# purple_v2.net
KiCad netlist of a schematic drawn in EAGLE
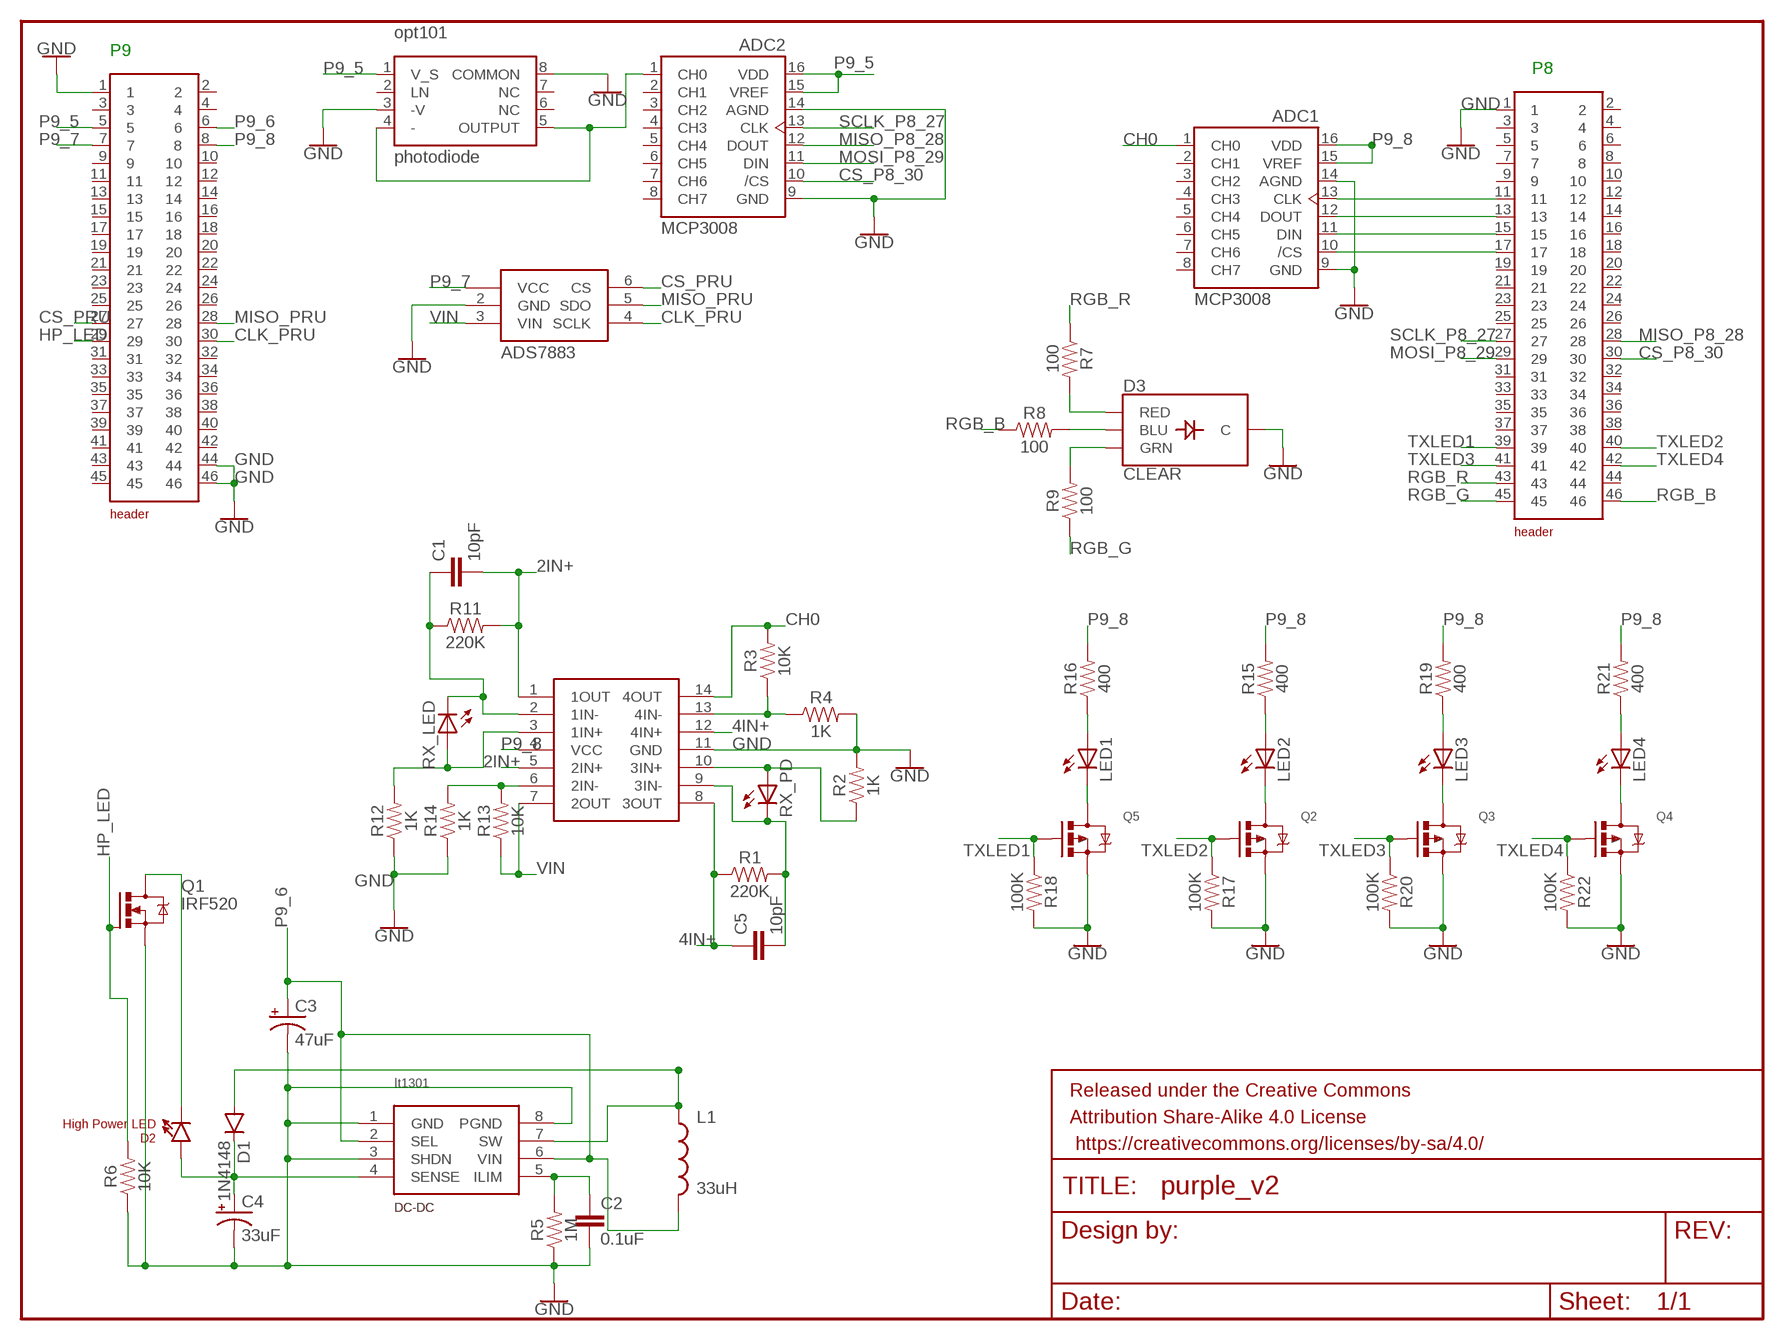
[diagram p0: schematic, sheet 1]

(export (version "E")
  (design (tool "Eeschema 10.0.6"))
  (components
    (comp (ref "ADC1")
      (value "MCP3008-SO16")
      (footprint "eagle-import:SO16")
      (libsource (lib "eagle-import") (part "MCP3008-SO16"))
    )
    (comp (ref "ADC2")
      (value "MCP3008-SO16")
      (footprint "eagle-import:SO16")
      (libsource (lib "eagle-import") (part "MCP3008-SO16"))
    )
    (comp (ref "C1")
      (value "10pF")
      (footprint "eagle-import:0603")
      (libsource (lib "eagle-import") (part "10PF-0603-50V-5%"))
    )
    (comp (ref "C2")
      (value "0.1uF")
      (footprint "eagle-import:CAP-PTH-SMALL")
      (libsource (lib "eagle-import") (part "CAPPTH"))
    )
    (comp (ref "C3")
      (value "47uF")
      (footprint "eagle-import:CPOL-RADIAL-10UF-25V")
      (libsource (lib "eagle-import") (part "CAP_POLPTH2"))
    )
    (comp (ref "C4")
      (value "33uF")
      (footprint "eagle-import:CPOL-RADIAL-10UF-25V")
      (libsource (lib "eagle-import") (part "CAP_POLPTH2"))
    )
    (comp (ref "C5")
      (value "10pF")
      (footprint "eagle-import:0603")
      (libsource (lib "eagle-import") (part "10PF-0603-50V-5%"))
    )
    (comp (ref "D1")
      (value "1N4148")
      (footprint "eagle-import:DIODE-1N4148")
      (libsource (lib "eagle-import") (part "DIODE1N4148"))
    )
    (comp (ref "D2")
      (value "High Power LED")
      (footprint "eagle-import:LTE-302")
      (libsource (lib "eagle-import") (part "LTE-302"))
    )
    (comp (ref "D3")
      (value "CLEAR")
      (footprint "eagle-import:LED-RGB-THRU")
      (libsource (lib "eagle-import") (part "LED-RGB-CCCLEAR"))
    )
    (comp (ref "FRAME1")
      (value "FRAME-LETTERNO_PACKAGE")
      (footprint "eagle-import:DUMMY")
      (fields (field (name "DESIGNER") "Nobody"))
      (libsource (lib "eagle-import") (part "FRAME-LETTERNO_PACKAGE"))
    )
    (comp (ref "J1")
      (value "223")
      (footprint "eagle-import:2_23")
      (libsource (lib "eagle-import") (part "223"))
    )
    (comp (ref "J2")
      (value "223")
      (footprint "eagle-import:2_23")
      (libsource (lib "eagle-import") (part "223"))
    )
    (comp (ref "L1")
      (value "33uH")
      (footprint "eagle-import:RLB0912")
      (libsource (lib "eagle-import") (part "INDUCTORRLB0912"))
    )
    (comp (ref "LED1")
      (value "LED5MM")
      (footprint "eagle-import:LED5MM")
      (libsource (lib "eagle-import") (part "LED5MM"))
    )
    (comp (ref "LED2")
      (value "LED5MM")
      (footprint "eagle-import:LED5MM")
      (libsource (lib "eagle-import") (part "LED5MM"))
    )
    (comp (ref "LED3")
      (value "LED5MM")
      (footprint "eagle-import:LED5MM")
      (libsource (lib "eagle-import") (part "LED5MM"))
    )
    (comp (ref "LED4")
      (value "LED5MM")
      (footprint "eagle-import:LED5MM")
      (libsource (lib "eagle-import") (part "LED5MM"))
    )
    (comp (ref "OP-AMP")
      (value "TLC2274-SO14")
      (footprint "eagle-import:SO14")
      (libsource (lib "eagle-import") (part "TLC2274-SO14"))
    )
    (comp (ref "Q1")
      (value "IRF520")
      (footprint "eagle-import:TO220BV")
      (libsource (lib "eagle-import") (part "IRF520"))
    )
    (comp (ref "Q2")
      (value "MOSFET-PCHANNEL")
      (footprint "eagle-import:SOT23-3")
      (libsource (lib "eagle-import") (part "MOSFET-PCHANNEL"))
    )
    (comp (ref "Q3")
      (value "MOSFET-PCHANNEL")
      (footprint "eagle-import:SOT23-3")
      (libsource (lib "eagle-import") (part "MOSFET-PCHANNEL"))
    )
    (comp (ref "Q4")
      (value "MOSFET-PCHANNEL")
      (footprint "eagle-import:SOT23-3")
      (libsource (lib "eagle-import") (part "MOSFET-PCHANNEL"))
    )
    (comp (ref "Q5")
      (value "MOSFET-PCHANNEL")
      (footprint "eagle-import:SOT23-3")
      (libsource (lib "eagle-import") (part "MOSFET-PCHANNEL"))
    )
    (comp (ref "R1")
      (value "220K")
      (footprint "eagle-import:0805")
      (libsource (lib "eagle-import") (part "0.3OHM-0805-1/8W-1%"))
    )
    (comp (ref "R2")
      (value "1K")
      (footprint "eagle-import:0805")
      (libsource (lib "eagle-import") (part "0.3OHM-0805-1/8W-1%"))
    )
    (comp (ref "R3")
      (value "10K")
      (footprint "eagle-import:0805")
      (libsource (lib "eagle-import") (part "0.3OHM-0805-1/8W-1%"))
    )
    (comp (ref "R4")
      (value "1K")
      (footprint "eagle-import:0805")
      (libsource (lib "eagle-import") (part "0.3OHM-0805-1/8W-1%"))
    )
    (comp (ref "R5")
      (value "1M")
      (footprint "eagle-import:0805")
      (libsource (lib "eagle-import") (part "0.3OHM-0805-1/8W-1%"))
    )
    (comp (ref "R6")
      (value "10K")
      (footprint "eagle-import:0805")
      (libsource (lib "eagle-import") (part "0.3OHM-0805-1/8W-1%"))
    )
    (comp (ref "R7")
      (value "100")
      (footprint "eagle-import:0805")
      (libsource (lib "eagle-import") (part "0.3OHM-0805-1/8W-1%"))
    )
    (comp (ref "R8")
      (value "100")
      (footprint "eagle-import:0805")
      (libsource (lib "eagle-import") (part "0.3OHM-0805-1/8W-1%"))
    )
    (comp (ref "R9")
      (value "100")
      (footprint "eagle-import:0805")
      (libsource (lib "eagle-import") (part "0.3OHM-0805-1/8W-1%"))
    )
    (comp (ref "R11")
      (value "220K")
      (footprint "eagle-import:0805")
      (libsource (lib "eagle-import") (part "0.3OHM-0805-1/8W-1%"))
    )
    (comp (ref "R12")
      (value "1K")
      (footprint "eagle-import:0805")
      (libsource (lib "eagle-import") (part "0.3OHM-0805-1/8W-1%"))
    )
    (comp (ref "R13")
      (value "10K")
      (footprint "eagle-import:0805")
      (libsource (lib "eagle-import") (part "0.3OHM-0805-1/8W-1%"))
    )
    (comp (ref "R14")
      (value "1K")
      (footprint "eagle-import:0805")
      (libsource (lib "eagle-import") (part "0.3OHM-0805-1/8W-1%"))
    )
    (comp (ref "R15")
      (value "400")
      (footprint "eagle-import:0805")
      (libsource (lib "eagle-import") (part "0.3OHM-0805-1/8W-1%"))
    )
    (comp (ref "R16")
      (value "400")
      (footprint "eagle-import:0805")
      (libsource (lib "eagle-import") (part "0.3OHM-0805-1/8W-1%"))
    )
    (comp (ref "R17")
      (value "100K")
      (footprint "eagle-import:0805")
      (libsource (lib "eagle-import") (part "0.3OHM-0805-1/8W-1%"))
    )
    (comp (ref "R18")
      (value "100K")
      (footprint "eagle-import:0805")
      (libsource (lib "eagle-import") (part "0.3OHM-0805-1/8W-1%"))
    )
    (comp (ref "R19")
      (value "400")
      (footprint "eagle-import:0805")
      (libsource (lib "eagle-import") (part "0.3OHM-0805-1/8W-1%"))
    )
    (comp (ref "R20")
      (value "100K")
      (footprint "eagle-import:0805")
      (libsource (lib "eagle-import") (part "0.3OHM-0805-1/8W-1%"))
    )
    (comp (ref "R21")
      (value "400")
      (footprint "eagle-import:0805")
      (libsource (lib "eagle-import") (part "0.3OHM-0805-1/8W-1%"))
    )
    (comp (ref "R22")
      (value "100K")
      (footprint "eagle-import:0805")
      (libsource (lib "eagle-import") (part "0.3OHM-0805-1/8W-1%"))
    )
    (comp (ref "RX_LED")
      (value "LED5MM")
      (footprint "eagle-import:LED5MM")
      (libsource (lib "eagle-import") (part "LED5MM"))
    )
    (comp (ref "RX_PD")
      (value "LED5MM")
      (footprint "eagle-import:LED5MM")
      (libsource (lib "eagle-import") (part "LED5MM"))
    )
    (comp (ref "U$1")
      (value "ADS7883")
      (footprint "eagle-import:SOT23-6")
      (libsource (lib "eagle-import") (part "ADS7883"))
    )
    (comp (ref "U5")
      (value "LT1301")
      (footprint "eagle-import:DIL08")
      (libsource (lib "eagle-import") (part "LT1301"))
    )
    (comp (ref "U9")
      (value "OPT101")
      (footprint "eagle-import:OPT101")
      (libsource (lib "eagle-import") (part "OPT101"))
    )
  )
  (nets
    (net (code "1") (name "/2IN+") (class "Default")
      (node (ref "C1") (pin "2") (pinfunction "2_2") (pintype "passive"))
      (node (ref "OP-AMP") (pin "1") (pinfunction "1OUT_1") (pintype "bidirectional"))
      (node (ref "OP-AMP") (pin "5") (pinfunction "2IN+_5") (pintype "bidirectional"))
      (node (ref "R11") (pin "2") (pinfunction "2_2") (pintype "passive"))
    )
    (net (code "2") (name "/4IN+") (class "Default")
      (node (ref "C5") (pin "1") (pinfunction "1_1") (pintype "passive"))
      (node (ref "OP-AMP") (pin "12") (pinfunction "4IN+_12") (pintype "bidirectional"))
      (node (ref "OP-AMP") (pin "8") (pinfunction "3OUT_8") (pintype "bidirectional"))
      (node (ref "R1") (pin "1") (pinfunction "1_1") (pintype "passive"))
    )
    (net (code "3") (name "/CH0") (class "Default")
      (node (ref "ADC1") (pin "1") (pinfunction "CH0_1") (pintype "input"))
      (node (ref "OP-AMP") (pin "14") (pinfunction "4OUT_14") (pintype "bidirectional"))
      (node (ref "R3") (pin "2") (pinfunction "2_2") (pintype "passive"))
    )
    (net (code "4") (name "/CLK_PRU") (class "Default")
      (node (ref "J1") (pin "30") (pinfunction "30_30") (pintype "bidirectional"))
      (node (ref "U$1") (pin "4") (pinfunction "SCLK_4") (pintype "bidirectional"))
    )
    (net (code "5") (name "/CS_P8_30") (class "Default")
      (node (ref "ADC2") (pin "10") (pinfunction "/CS_10") (pintype "bidirectional"))
      (node (ref "J2") (pin "30") (pinfunction "30_30") (pintype "bidirectional"))
    )
    (net (code "6") (name "/CS_PRU") (class "Default")
      (node (ref "J1") (pin "27") (pinfunction "27_27") (pintype "bidirectional"))
      (node (ref "U$1") (pin "6") (pinfunction "CS_6") (pintype "bidirectional"))
    )
    (net (code "7") (name "/HP_LED") (class "Default")
      (node (ref "J1") (pin "29") (pinfunction "29_29") (pintype "bidirectional"))
      (node (ref "Q1") (pin "G") (pinfunction "G_G") (pintype "passive"))
      (node (ref "R6") (pin "2") (pinfunction "2_2") (pintype "passive"))
    )
    (net (code "8") (name "/MISO_P8_28") (class "Default")
      (node (ref "ADC2") (pin "12") (pinfunction "DOUT_12") (pintype "output"))
      (node (ref "J2") (pin "28") (pinfunction "28_28") (pintype "bidirectional"))
    )
    (net (code "9") (name "/MISO_PRU") (class "Default")
      (node (ref "J1") (pin "28") (pinfunction "28_28") (pintype "bidirectional"))
      (node (ref "U$1") (pin "5") (pinfunction "SDO_5") (pintype "bidirectional"))
    )
    (net (code "10") (name "/MOSI_P8_29") (class "Default")
      (node (ref "ADC2") (pin "11") (pinfunction "DIN_11") (pintype "input"))
      (node (ref "J2") (pin "29") (pinfunction "29_29") (pintype "bidirectional"))
    )
    (net (code "11") (name "/P9_5") (class "Default")
      (node (ref "ADC2") (pin "15") (pinfunction "VREF_15") (pintype "input"))
      (node (ref "ADC2") (pin "16") (pinfunction "VDD_16") (pintype "power_in"))
      (node (ref "J1") (pin "5") (pinfunction "5_5") (pintype "bidirectional"))
      (node (ref "U9") (pin "1") (pinfunction "V_S_1") (pintype "power_in"))
    )
    (net (code "12") (name "/P9_6") (class "Default")
      (node (ref "C3") (pin "1") (pinfunction "+_1") (pintype "passive"))
      (node (ref "J1") (pin "6") (pinfunction "6_6") (pintype "bidirectional"))
      (node (ref "L1") (pin "2") (pinfunction "2_2") (pintype "passive"))
      (node (ref "U5") (pin "2") (pinfunction "SEL_2") (pintype "bidirectional"))
      (node (ref "U5") (pin "6") (pinfunction "VIN_6") (pintype "bidirectional"))
    )
    (net (code "13") (name "/P9_7") (class "Default")
      (node (ref "J1") (pin "7") (pinfunction "7_7") (pintype "bidirectional"))
      (node (ref "U$1") (pin "1") (pinfunction "VCC_1") (pintype "bidirectional"))
    )
    (net (code "14") (name "/P9_8") (class "Default")
      (node (ref "ADC1") (pin "15") (pinfunction "VREF_15") (pintype "input"))
      (node (ref "ADC1") (pin "16") (pinfunction "VDD_16") (pintype "power_in"))
      (node (ref "J1") (pin "8") (pinfunction "8_8") (pintype "bidirectional"))
      (node (ref "OP-AMP") (pin "4") (pinfunction "VCC_4") (pintype "bidirectional"))
      (node (ref "R15") (pin "2") (pinfunction "2_2") (pintype "passive"))
      (node (ref "R16") (pin "2") (pinfunction "2_2") (pintype "passive"))
      (node (ref "R19") (pin "2") (pinfunction "2_2") (pintype "passive"))
      (node (ref "R21") (pin "2") (pinfunction "2_2") (pintype "passive"))
    )
    (net (code "15") (name "/RGB_B") (class "Default")
      (node (ref "J2") (pin "46") (pinfunction "46_46") (pintype "bidirectional"))
      (node (ref "R8") (pin "1") (pinfunction "1_1") (pintype "passive"))
    )
    (net (code "16") (name "/RGB_G") (class "Default")
      (node (ref "J2") (pin "45") (pinfunction "45_45") (pintype "bidirectional"))
      (node (ref "R9") (pin "1") (pinfunction "1_1") (pintype "passive"))
    )
    (net (code "17") (name "/RGB_R") (class "Default")
      (node (ref "J2") (pin "43") (pinfunction "43_43") (pintype "bidirectional"))
      (node (ref "R7") (pin "1") (pinfunction "1_1") (pintype "passive"))
    )
    (net (code "18") (name "/SCLK_P8_27") (class "Default")
      (node (ref "ADC2") (pin "13") (pinfunction "CLK_13") (pintype "input"))
      (node (ref "J2") (pin "27") (pinfunction "27_27") (pintype "bidirectional"))
    )
    (net (code "19") (name "/TXLED1") (class "Default")
      (node (ref "J2") (pin "39") (pinfunction "39_39") (pintype "bidirectional"))
      (node (ref "Q5") (pin "1") (pinfunction "G_1") (pintype "passive"))
      (node (ref "R18") (pin "1") (pinfunction "1_1") (pintype "passive"))
    )
    (net (code "20") (name "/TXLED2") (class "Default")
      (node (ref "J2") (pin "40") (pinfunction "40_40") (pintype "bidirectional"))
      (node (ref "Q2") (pin "1") (pinfunction "G_1") (pintype "passive"))
      (node (ref "R17") (pin "1") (pinfunction "1_1") (pintype "passive"))
    )
    (net (code "21") (name "/TXLED3") (class "Default")
      (node (ref "J2") (pin "41") (pinfunction "41_41") (pintype "bidirectional"))
      (node (ref "Q3") (pin "1") (pinfunction "G_1") (pintype "passive"))
      (node (ref "R20") (pin "1") (pinfunction "1_1") (pintype "passive"))
    )
    (net (code "22") (name "/TXLED4") (class "Default")
      (node (ref "J2") (pin "42") (pinfunction "42_42") (pintype "bidirectional"))
      (node (ref "Q4") (pin "1") (pinfunction "G_1") (pintype "passive"))
      (node (ref "R22") (pin "1") (pinfunction "1_1") (pintype "passive"))
    )
    (net (code "23") (name "/VIN") (class "Default")
      (node (ref "OP-AMP") (pin "7") (pinfunction "2OUT_7") (pintype "bidirectional"))
      (node (ref "R13") (pin "1") (pinfunction "1_1") (pintype "passive"))
      (node (ref "U$1") (pin "3") (pinfunction "VIN_3") (pintype "bidirectional"))
    )
    (net (code "24") (name "GND") (class "Default")
      (node (ref "ADC1") (pin "14") (pinfunction "AGND_14") (pintype "power_in"))
      (node (ref "ADC1") (pin "9") (pinfunction "GND_9") (pintype "power_in"))
      (node (ref "ADC2") (pin "14") (pinfunction "AGND_14") (pintype "power_in"))
      (node (ref "ADC2") (pin "9") (pinfunction "GND_9") (pintype "power_in"))
      (node (ref "C2") (pin "2") (pinfunction "2_2") (pintype "passive"))
      (node (ref "C3") (pin "2") (pinfunction "-_2") (pintype "passive"))
      (node (ref "C4") (pin "2") (pinfunction "-_2") (pintype "passive"))
      (node (ref "D3") (pin "2") (pinfunction "C_2") (pintype "bidirectional"))
      (node (ref "J1") (pin "1") (pinfunction "1_1") (pintype "bidirectional"))
      (node (ref "J1") (pin "44") (pinfunction "44_44") (pintype "bidirectional"))
      (node (ref "J1") (pin "46") (pinfunction "46_46") (pintype "bidirectional"))
      (node (ref "J2") (pin "1") (pinfunction "1_1") (pintype "bidirectional"))
      (node (ref "OP-AMP") (pin "11") (pinfunction "GND_11") (pintype "bidirectional"))
      (node (ref "Q1") (pin "S") (pinfunction "S_S") (pintype "passive"))
      (node (ref "Q2") (pin "2") (pinfunction "S_2") (pintype "passive"))
      (node (ref "Q3") (pin "2") (pinfunction "S_2") (pintype "passive"))
      (node (ref "Q4") (pin "2") (pinfunction "S_2") (pintype "passive"))
      (node (ref "Q5") (pin "2") (pinfunction "S_2") (pintype "passive"))
      (node (ref "R12") (pin "1") (pinfunction "1_1") (pintype "passive"))
      (node (ref "R14") (pin "1") (pinfunction "1_1") (pintype "passive"))
      (node (ref "R17") (pin "2") (pinfunction "2_2") (pintype "passive"))
      (node (ref "R18") (pin "2") (pinfunction "2_2") (pintype "passive"))
      (node (ref "R2") (pin "2") (pinfunction "2_2") (pintype "passive"))
      (node (ref "R20") (pin "2") (pinfunction "2_2") (pintype "passive"))
      (node (ref "R22") (pin "2") (pinfunction "2_2") (pintype "passive"))
      (node (ref "R4") (pin "2") (pinfunction "2_2") (pintype "passive"))
      (node (ref "R5") (pin "1") (pinfunction "1_1") (pintype "passive"))
      (node (ref "R6") (pin "1") (pinfunction "1_1") (pintype "passive"))
      (node (ref "U$1") (pin "2") (pinfunction "GND_2") (pintype "bidirectional"))
      (node (ref "U5") (pin "1") (pinfunction "GND_1") (pintype "bidirectional"))
      (node (ref "U5") (pin "3") (pinfunction "SHDN_3") (pintype "bidirectional"))
      (node (ref "U5") (pin "8") (pinfunction "PGND_8") (pintype "bidirectional"))
      (node (ref "U9") (pin "3") (pinfunction "-V_3") (pintype "power_in"))
      (node (ref "U9") (pin "8") (pinfunction "COMMON_8") (pintype "power_in"))
    )
    (net (code "25") (name "Net-(ADC1-CLK)") (class "Default")
      (node (ref "ADC1") (pin "13") (pinfunction "CLK_13") (pintype "input"))
      (node (ref "J2") (pin "11") (pinfunction "11_11") (pintype "bidirectional"))
    )
    (net (code "26") (name "Net-(ADC1-DIN)") (class "Default")
      (node (ref "ADC1") (pin "11") (pinfunction "DIN_11") (pintype "input"))
      (node (ref "J2") (pin "15") (pinfunction "15_15") (pintype "bidirectional"))
    )
    (net (code "27") (name "Net-(ADC1-DOUT)") (class "Default")
      (node (ref "ADC1") (pin "12") (pinfunction "DOUT_12") (pintype "output"))
      (node (ref "J2") (pin "13") (pinfunction "13_13") (pintype "bidirectional"))
    )
    (net (code "28") (name "Net-(ADC1-{slash}CS)") (class "Default")
      (node (ref "ADC1") (pin "10") (pinfunction "/CS_10") (pintype "bidirectional"))
      (node (ref "J2") (pin "17") (pinfunction "17_17") (pintype "bidirectional"))
    )
    (net (code "29") (name "Net-(ADC2-CH0)") (class "Default")
      (node (ref "ADC2") (pin "1") (pinfunction "CH0_1") (pintype "input"))
      (node (ref "U9") (pin "4") (pinfunction "-_4") (pintype "bidirectional"))
      (node (ref "U9") (pin "5") (pinfunction "OUTPUT_5") (pintype "bidirectional"))
    )
    (net (code "30") (name "Net-(C4-+)") (class "Default")
      (node (ref "C4") (pin "1") (pinfunction "+_1") (pintype "passive"))
      (node (ref "D1") (pin "C") (pinfunction "C_C") (pintype "passive"))
      (node (ref "D2") (pin "A") (pinfunction "A_A") (pintype "bidirectional"))
      (node (ref "U5") (pin "4") (pinfunction "SENSE_4") (pintype "bidirectional"))
    )
    (net (code "31") (name "Net-(D2-PadC)") (class "Default")
      (node (ref "D2") (pin "C") (pinfunction "C_C") (pintype "bidirectional"))
      (node (ref "Q1") (pin "D") (pinfunction "D_D") (pintype "passive"))
    )
    (net (code "32") (name "Net-(D3-BLU)") (class "Default")
      (node (ref "D3") (pin "4") (pinfunction "BLU_4") (pintype "bidirectional"))
      (node (ref "R8") (pin "2") (pinfunction "2_2") (pintype "passive"))
    )
    (net (code "33") (name "Net-(D3-GRN)") (class "Default")
      (node (ref "D3") (pin "3") (pinfunction "GRN_3") (pintype "bidirectional"))
      (node (ref "R9") (pin "2") (pinfunction "2_2") (pintype "passive"))
    )
    (net (code "34") (name "Net-(D3-RED)") (class "Default")
      (node (ref "D3") (pin "1") (pinfunction "RED_1") (pintype "bidirectional"))
      (node (ref "R7") (pin "2") (pinfunction "2_2") (pintype "passive"))
    )
    (net (code "35") (name "Net-(LED1-C)") (class "Default")
      (node (ref "LED1") (pin "K") (pinfunction "C_K") (pintype "passive"))
      (node (ref "Q5") (pin "3") (pinfunction "D_3") (pintype "passive"))
    )
    (net (code "36") (name "Net-(LED1-PadA)") (class "Default")
      (node (ref "LED1") (pin "A") (pinfunction "A_A") (pintype "passive"))
      (node (ref "R16") (pin "1") (pinfunction "1_1") (pintype "passive"))
    )
    (net (code "37") (name "Net-(LED2-C)") (class "Default")
      (node (ref "LED2") (pin "K") (pinfunction "C_K") (pintype "passive"))
      (node (ref "Q2") (pin "3") (pinfunction "D_3") (pintype "passive"))
    )
    (net (code "38") (name "Net-(LED2-PadA)") (class "Default")
      (node (ref "LED2") (pin "A") (pinfunction "A_A") (pintype "passive"))
      (node (ref "R15") (pin "1") (pinfunction "1_1") (pintype "passive"))
    )
    (net (code "39") (name "Net-(LED3-C)") (class "Default")
      (node (ref "LED3") (pin "K") (pinfunction "C_K") (pintype "passive"))
      (node (ref "Q3") (pin "3") (pinfunction "D_3") (pintype "passive"))
    )
    (net (code "40") (name "Net-(LED3-PadA)") (class "Default")
      (node (ref "LED3") (pin "A") (pinfunction "A_A") (pintype "passive"))
      (node (ref "R19") (pin "1") (pinfunction "1_1") (pintype "passive"))
    )
    (net (code "41") (name "Net-(LED4-C)") (class "Default")
      (node (ref "LED4") (pin "K") (pinfunction "C_K") (pintype "passive"))
      (node (ref "Q4") (pin "3") (pinfunction "D_3") (pintype "passive"))
    )
    (net (code "42") (name "Net-(LED4-PadA)") (class "Default")
      (node (ref "LED4") (pin "A") (pinfunction "A_A") (pintype "passive"))
      (node (ref "R21") (pin "1") (pinfunction "1_1") (pintype "passive"))
    )
    (net (code "43") (name "Net-(OP-AMP-1IN+)") (class "Default")
      (node (ref "OP-AMP") (pin "3") (pinfunction "1IN+_3") (pintype "bidirectional"))
      (node (ref "R12") (pin "2") (pinfunction "2_2") (pintype "passive"))
      (node (ref "RX_LED") (pin "A") (pinfunction "A_A") (pintype "passive"))
    )
    (net (code "44") (name "Net-(OP-AMP-1IN-)") (class "Default")
      (node (ref "C1") (pin "1") (pinfunction "1_1") (pintype "passive"))
      (node (ref "OP-AMP") (pin "2") (pinfunction "1IN-_2") (pintype "bidirectional"))
      (node (ref "R11") (pin "1") (pinfunction "1_1") (pintype "passive"))
      (node (ref "RX_LED") (pin "K") (pinfunction "C_K") (pintype "passive"))
    )
    (net (code "45") (name "Net-(OP-AMP-2IN-)") (class "Default")
      (node (ref "OP-AMP") (pin "6") (pinfunction "2IN-_6") (pintype "bidirectional"))
      (node (ref "R13") (pin "2") (pinfunction "2_2") (pintype "passive"))
      (node (ref "R14") (pin "2") (pinfunction "2_2") (pintype "passive"))
    )
    (net (code "46") (name "Net-(OP-AMP-3IN+)") (class "Default")
      (node (ref "OP-AMP") (pin "10") (pinfunction "3IN+_10") (pintype "bidirectional"))
      (node (ref "R2") (pin "1") (pinfunction "1_1") (pintype "passive"))
      (node (ref "RX_PD") (pin "A") (pinfunction "A_A") (pintype "passive"))
    )
    (net (code "47") (name "Net-(OP-AMP-3IN-)") (class "Default")
      (node (ref "C5") (pin "2") (pinfunction "2_2") (pintype "passive"))
      (node (ref "OP-AMP") (pin "9") (pinfunction "3IN-_9") (pintype "bidirectional"))
      (node (ref "R1") (pin "2") (pinfunction "2_2") (pintype "passive"))
      (node (ref "RX_PD") (pin "K") (pinfunction "C_K") (pintype "passive"))
    )
    (net (code "48") (name "Net-(OP-AMP-4IN-)") (class "Default")
      (node (ref "OP-AMP") (pin "13") (pinfunction "4IN-_13") (pintype "bidirectional"))
      (node (ref "R3") (pin "1") (pinfunction "1_1") (pintype "passive"))
      (node (ref "R4") (pin "1") (pinfunction "1_1") (pintype "passive"))
    )
    (net (code "49") (name "Net-(U5-ILIM)") (class "Default")
      (node (ref "C2") (pin "1") (pinfunction "1_1") (pintype "passive"))
      (node (ref "R5") (pin "2") (pinfunction "2_2") (pintype "passive"))
      (node (ref "U5") (pin "5") (pinfunction "ILIM_5") (pintype "bidirectional"))
    )
    (net (code "50") (name "Net-(U5-SW)") (class "Default")
      (node (ref "D1") (pin "A") (pinfunction "A_A") (pintype "passive"))
      (node (ref "L1") (pin "1") (pinfunction "1_1") (pintype "passive"))
      (node (ref "U5") (pin "7") (pinfunction "SW_7") (pintype "bidirectional"))
    )
    (net (code "51") (name "unconnected-(ADC1-CH1-Pad2)") (class "Default")
      (node (ref "ADC1") (pin "2") (pinfunction "CH1_2") (pintype "input"))
    )
    (net (code "52") (name "unconnected-(ADC1-CH2-Pad3)") (class "Default")
      (node (ref "ADC1") (pin "3") (pinfunction "CH2_3") (pintype "input"))
    )
    (net (code "53") (name "unconnected-(ADC1-CH3-Pad4)") (class "Default")
      (node (ref "ADC1") (pin "4") (pinfunction "CH3_4") (pintype "input"))
    )
    (net (code "54") (name "unconnected-(ADC1-CH4-Pad5)") (class "Default")
      (node (ref "ADC1") (pin "5") (pinfunction "CH4_5") (pintype "input"))
    )
    (net (code "55") (name "unconnected-(ADC1-CH5-Pad6)") (class "Default")
      (node (ref "ADC1") (pin "6") (pinfunction "CH5_6") (pintype "input"))
    )
    (net (code "56") (name "unconnected-(ADC1-CH6-Pad7)") (class "Default")
      (node (ref "ADC1") (pin "7") (pinfunction "CH6_7") (pintype "input"))
    )
    (net (code "57") (name "unconnected-(ADC1-CH7-Pad8)") (class "Default")
      (node (ref "ADC1") (pin "8") (pinfunction "CH7_8") (pintype "input"))
    )
    (net (code "58") (name "unconnected-(ADC2-CH1-Pad2)") (class "Default")
      (node (ref "ADC2") (pin "2") (pinfunction "CH1_2") (pintype "input"))
    )
    (net (code "59") (name "unconnected-(ADC2-CH2-Pad3)") (class "Default")
      (node (ref "ADC2") (pin "3") (pinfunction "CH2_3") (pintype "input"))
    )
    (net (code "60") (name "unconnected-(ADC2-CH3-Pad4)") (class "Default")
      (node (ref "ADC2") (pin "4") (pinfunction "CH3_4") (pintype "input"))
    )
    (net (code "61") (name "unconnected-(ADC2-CH4-Pad5)") (class "Default")
      (node (ref "ADC2") (pin "5") (pinfunction "CH4_5") (pintype "input"))
    )
    (net (code "62") (name "unconnected-(ADC2-CH5-Pad6)") (class "Default")
      (node (ref "ADC2") (pin "6") (pinfunction "CH5_6") (pintype "input"))
    )
    (net (code "63") (name "unconnected-(ADC2-CH6-Pad7)") (class "Default")
      (node (ref "ADC2") (pin "7") (pinfunction "CH6_7") (pintype "input"))
    )
    (net (code "64") (name "unconnected-(ADC2-CH7-Pad8)") (class "Default")
      (node (ref "ADC2") (pin "8") (pinfunction "CH7_8") (pintype "input"))
    )
    (net (code "65") (name "unconnected-(J1-Pad2)") (class "Default")
      (node (ref "J1") (pin "2") (pinfunction "2_2") (pintype "bidirectional"))
    )
    (net (code "66") (name "unconnected-(J1-Pad3)") (class "Default")
      (node (ref "J1") (pin "3") (pinfunction "3_3") (pintype "bidirectional"))
    )
    (net (code "67") (name "unconnected-(J1-Pad4)") (class "Default")
      (node (ref "J1") (pin "4") (pinfunction "4_4") (pintype "bidirectional"))
    )
    (net (code "68") (name "unconnected-(J1-Pad9)") (class "Default")
      (node (ref "J1") (pin "9") (pinfunction "9_9") (pintype "bidirectional"))
    )
    (net (code "69") (name "unconnected-(J1-Pad10)") (class "Default")
      (node (ref "J1") (pin "10") (pinfunction "10_10") (pintype "bidirectional"))
    )
    (net (code "70") (name "unconnected-(J1-Pad11)") (class "Default")
      (node (ref "J1") (pin "11") (pinfunction "11_11") (pintype "bidirectional"))
    )
    (net (code "71") (name "unconnected-(J1-Pad12)") (class "Default")
      (node (ref "J1") (pin "12") (pinfunction "12_12") (pintype "bidirectional"))
    )
    (net (code "72") (name "unconnected-(J1-Pad13)") (class "Default")
      (node (ref "J1") (pin "13") (pinfunction "13_13") (pintype "bidirectional"))
    )
    (net (code "73") (name "unconnected-(J1-Pad14)") (class "Default")
      (node (ref "J1") (pin "14") (pinfunction "14_14") (pintype "bidirectional"))
    )
    (net (code "74") (name "unconnected-(J1-Pad15)") (class "Default")
      (node (ref "J1") (pin "15") (pinfunction "15_15") (pintype "bidirectional"))
    )
    (net (code "75") (name "unconnected-(J1-Pad16)") (class "Default")
      (node (ref "J1") (pin "16") (pinfunction "16_16") (pintype "bidirectional"))
    )
    (net (code "76") (name "unconnected-(J1-Pad17)") (class "Default")
      (node (ref "J1") (pin "17") (pinfunction "17_17") (pintype "bidirectional"))
    )
    (net (code "77") (name "unconnected-(J1-Pad18)") (class "Default")
      (node (ref "J1") (pin "18") (pinfunction "18_18") (pintype "bidirectional"))
    )
    (net (code "78") (name "unconnected-(J1-Pad19)") (class "Default")
      (node (ref "J1") (pin "19") (pinfunction "19_19") (pintype "bidirectional"))
    )
    (net (code "79") (name "unconnected-(J1-Pad20)") (class "Default")
      (node (ref "J1") (pin "20") (pinfunction "20_20") (pintype "bidirectional"))
    )
    (net (code "80") (name "unconnected-(J1-Pad21)") (class "Default")
      (node (ref "J1") (pin "21") (pinfunction "21_21") (pintype "bidirectional"))
    )
    (net (code "81") (name "unconnected-(J1-Pad22)") (class "Default")
      (node (ref "J1") (pin "22") (pinfunction "22_22") (pintype "bidirectional"))
    )
    (net (code "82") (name "unconnected-(J1-Pad23)") (class "Default")
      (node (ref "J1") (pin "23") (pinfunction "23_23") (pintype "bidirectional"))
    )
    (net (code "83") (name "unconnected-(J1-Pad24)") (class "Default")
      (node (ref "J1") (pin "24") (pinfunction "24_24") (pintype "bidirectional"))
    )
    (net (code "84") (name "unconnected-(J1-Pad25)") (class "Default")
      (node (ref "J1") (pin "25") (pinfunction "25_25") (pintype "bidirectional"))
    )
    (net (code "85") (name "unconnected-(J1-Pad26)") (class "Default")
      (node (ref "J1") (pin "26") (pinfunction "26_26") (pintype "bidirectional"))
    )
    (net (code "86") (name "unconnected-(J1-Pad31)") (class "Default")
      (node (ref "J1") (pin "31") (pinfunction "31_31") (pintype "bidirectional"))
    )
    (net (code "87") (name "unconnected-(J1-Pad32)") (class "Default")
      (node (ref "J1") (pin "32") (pinfunction "32_32") (pintype "bidirectional"))
    )
    (net (code "88") (name "unconnected-(J1-Pad33)") (class "Default")
      (node (ref "J1") (pin "33") (pinfunction "33_33") (pintype "bidirectional"))
    )
    (net (code "89") (name "unconnected-(J1-Pad34)") (class "Default")
      (node (ref "J1") (pin "34") (pinfunction "34_34") (pintype "bidirectional"))
    )
    (net (code "90") (name "unconnected-(J1-Pad35)") (class "Default")
      (node (ref "J1") (pin "35") (pinfunction "35_35") (pintype "bidirectional"))
    )
    (net (code "91") (name "unconnected-(J1-Pad36)") (class "Default")
      (node (ref "J1") (pin "36") (pinfunction "36_36") (pintype "bidirectional"))
    )
    (net (code "92") (name "unconnected-(J1-Pad37)") (class "Default")
      (node (ref "J1") (pin "37") (pinfunction "37_37") (pintype "bidirectional"))
    )
    (net (code "93") (name "unconnected-(J1-Pad38)") (class "Default")
      (node (ref "J1") (pin "38") (pinfunction "38_38") (pintype "bidirectional"))
    )
    (net (code "94") (name "unconnected-(J1-Pad39)") (class "Default")
      (node (ref "J1") (pin "39") (pinfunction "39_39") (pintype "bidirectional"))
    )
    (net (code "95") (name "unconnected-(J1-Pad40)") (class "Default")
      (node (ref "J1") (pin "40") (pinfunction "40_40") (pintype "bidirectional"))
    )
    (net (code "96") (name "unconnected-(J1-Pad41)") (class "Default")
      (node (ref "J1") (pin "41") (pinfunction "41_41") (pintype "bidirectional"))
    )
    (net (code "97") (name "unconnected-(J1-Pad42)") (class "Default")
      (node (ref "J1") (pin "42") (pinfunction "42_42") (pintype "bidirectional"))
    )
    (net (code "98") (name "unconnected-(J1-Pad43)") (class "Default")
      (node (ref "J1") (pin "43") (pinfunction "43_43") (pintype "bidirectional"))
    )
    (net (code "99") (name "unconnected-(J1-Pad45)") (class "Default")
      (node (ref "J1") (pin "45") (pinfunction "45_45") (pintype "bidirectional"))
    )
    (net (code "100") (name "unconnected-(J2-Pad2)") (class "Default")
      (node (ref "J2") (pin "2") (pinfunction "2_2") (pintype "bidirectional"))
    )
    (net (code "101") (name "unconnected-(J2-Pad3)") (class "Default")
      (node (ref "J2") (pin "3") (pinfunction "3_3") (pintype "bidirectional"))
    )
    (net (code "102") (name "unconnected-(J2-Pad4)") (class "Default")
      (node (ref "J2") (pin "4") (pinfunction "4_4") (pintype "bidirectional"))
    )
    (net (code "103") (name "unconnected-(J2-Pad5)") (class "Default")
      (node (ref "J2") (pin "5") (pinfunction "5_5") (pintype "bidirectional"))
    )
    (net (code "104") (name "unconnected-(J2-Pad6)") (class "Default")
      (node (ref "J2") (pin "6") (pinfunction "6_6") (pintype "bidirectional"))
    )
    (net (code "105") (name "unconnected-(J2-Pad7)") (class "Default")
      (node (ref "J2") (pin "7") (pinfunction "7_7") (pintype "bidirectional"))
    )
    (net (code "106") (name "unconnected-(J2-Pad8)") (class "Default")
      (node (ref "J2") (pin "8") (pinfunction "8_8") (pintype "bidirectional"))
    )
    (net (code "107") (name "unconnected-(J2-Pad9)") (class "Default")
      (node (ref "J2") (pin "9") (pinfunction "9_9") (pintype "bidirectional"))
    )
    (net (code "108") (name "unconnected-(J2-Pad10)") (class "Default")
      (node (ref "J2") (pin "10") (pinfunction "10_10") (pintype "bidirectional"))
    )
    (net (code "109") (name "unconnected-(J2-Pad12)") (class "Default")
      (node (ref "J2") (pin "12") (pinfunction "12_12") (pintype "bidirectional"))
    )
    (net (code "110") (name "unconnected-(J2-Pad14)") (class "Default")
      (node (ref "J2") (pin "14") (pinfunction "14_14") (pintype "bidirectional"))
    )
    (net (code "111") (name "unconnected-(J2-Pad16)") (class "Default")
      (node (ref "J2") (pin "16") (pinfunction "16_16") (pintype "bidirectional"))
    )
    (net (code "112") (name "unconnected-(J2-Pad18)") (class "Default")
      (node (ref "J2") (pin "18") (pinfunction "18_18") (pintype "bidirectional"))
    )
    (net (code "113") (name "unconnected-(J2-Pad19)") (class "Default")
      (node (ref "J2") (pin "19") (pinfunction "19_19") (pintype "bidirectional"))
    )
    (net (code "114") (name "unconnected-(J2-Pad20)") (class "Default")
      (node (ref "J2") (pin "20") (pinfunction "20_20") (pintype "bidirectional"))
    )
    (net (code "115") (name "unconnected-(J2-Pad21)") (class "Default")
      (node (ref "J2") (pin "21") (pinfunction "21_21") (pintype "bidirectional"))
    )
    (net (code "116") (name "unconnected-(J2-Pad22)") (class "Default")
      (node (ref "J2") (pin "22") (pinfunction "22_22") (pintype "bidirectional"))
    )
    (net (code "117") (name "unconnected-(J2-Pad23)") (class "Default")
      (node (ref "J2") (pin "23") (pinfunction "23_23") (pintype "bidirectional"))
    )
    (net (code "118") (name "unconnected-(J2-Pad24)") (class "Default")
      (node (ref "J2") (pin "24") (pinfunction "24_24") (pintype "bidirectional"))
    )
    (net (code "119") (name "unconnected-(J2-Pad25)") (class "Default")
      (node (ref "J2") (pin "25") (pinfunction "25_25") (pintype "bidirectional"))
    )
    (net (code "120") (name "unconnected-(J2-Pad26)") (class "Default")
      (node (ref "J2") (pin "26") (pinfunction "26_26") (pintype "bidirectional"))
    )
    (net (code "121") (name "unconnected-(J2-Pad31)") (class "Default")
      (node (ref "J2") (pin "31") (pinfunction "31_31") (pintype "bidirectional"))
    )
    (net (code "122") (name "unconnected-(J2-Pad32)") (class "Default")
      (node (ref "J2") (pin "32") (pinfunction "32_32") (pintype "bidirectional"))
    )
    (net (code "123") (name "unconnected-(J2-Pad33)") (class "Default")
      (node (ref "J2") (pin "33") (pinfunction "33_33") (pintype "bidirectional"))
    )
    (net (code "124") (name "unconnected-(J2-Pad34)") (class "Default")
      (node (ref "J2") (pin "34") (pinfunction "34_34") (pintype "bidirectional"))
    )
    (net (code "125") (name "unconnected-(J2-Pad35)") (class "Default")
      (node (ref "J2") (pin "35") (pinfunction "35_35") (pintype "bidirectional"))
    )
    (net (code "126") (name "unconnected-(J2-Pad36)") (class "Default")
      (node (ref "J2") (pin "36") (pinfunction "36_36") (pintype "bidirectional"))
    )
    (net (code "127") (name "unconnected-(J2-Pad37)") (class "Default")
      (node (ref "J2") (pin "37") (pinfunction "37_37") (pintype "bidirectional"))
    )
    (net (code "128") (name "unconnected-(J2-Pad38)") (class "Default")
      (node (ref "J2") (pin "38") (pinfunction "38_38") (pintype "bidirectional"))
    )
    (net (code "129") (name "unconnected-(J2-Pad44)") (class "Default")
      (node (ref "J2") (pin "44") (pinfunction "44_44") (pintype "bidirectional"))
    )
    (net (code "130") (name "unconnected-(U9-LN-Pad2)") (class "Default")
      (node (ref "U9") (pin "2") (pinfunction "LN_2") (pintype "no_connect"))
    )
    (net (code "131") (name "unconnected-(U9-NC-Pad6)") (class "Default")
      (node (ref "U9") (pin "6") (pinfunction "NC_6") (pintype "no_connect"))
    )
    (net (code "132") (name "unconnected-(U9-NC-Pad7)") (class "Default")
      (node (ref "U9") (pin "7") (pinfunction "NC_7") (pintype "no_connect"))
    )
  )
)
